# LightSensor.net
KiCad netlist of a schematic drawn in EAGLE
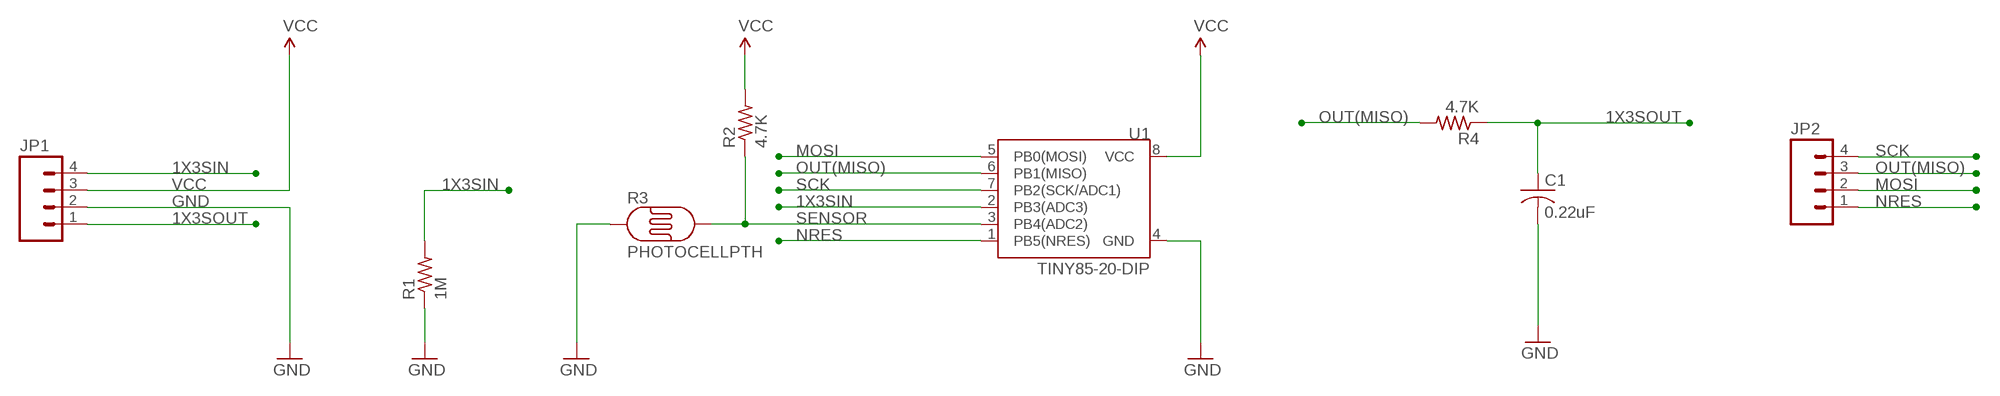
[diagram p0: schematic, sheet 1]

(export (version "E")
  (design (tool "Eeschema 10.0.6"))
  (components
    (comp (ref "C1")
      (value "0.22uF")
      (footprint "eagle-import:C0402")
      (libsource (lib "eagle-import") (part "C-USC0402"))
    )
    (comp (ref "JP1")
      (value "M04PTH")
      (footprint "eagle-import:1X04")
      (libsource (lib "eagle-import") (part "M04PTH"))
    )
    (comp (ref "JP2")
      (value "M04PTH")
      (footprint "eagle-import:1X04")
      (libsource (lib "eagle-import") (part "M04PTH"))
    )
    (comp (ref "R1")
      (value "1M")
      (footprint "eagle-import:R0603")
      (libsource (lib "eagle-import") (part "R-US_R0603"))
    )
    (comp (ref "R2")
      (value "4.7K")
      (footprint "eagle-import:R0603")
      (libsource (lib "eagle-import") (part "R-US_R0603"))
    )
    (comp (ref "R3")
      (value "PHOTOCELLPTH")
      (footprint "eagle-import:PHOTOCELL")
      (libsource (lib "eagle-import") (part "PHOTOCELLPTH"))
    )
    (comp (ref "R4")
      (value "4.7K")
      (footprint "eagle-import:R0603")
      (libsource (lib "eagle-import") (part "R-US_R0603"))
    )
    (comp (ref "U1")
      (value "TINY85-20-DIP")
      (footprint "eagle-import:DIP08")
      (libsource (lib "eagle-import") (part "ATTINY45TINY85-20-DIP"))
    )
  )
  (nets
    (net (code "1") (name "/1X3SIN") (class "Default")
      (node (ref "JP1") (pin "4") (pinfunction "4_4") (pintype "passive"))
      (node (ref "R1") (pin "2") (pinfunction "2_2") (pintype "passive"))
      (node (ref "U1") (pin "2") (pinfunction "PB3(ADC3)_2") (pintype "bidirectional"))
    )
    (net (code "2") (name "/1X3SOUT") (class "Default")
      (node (ref "C1") (pin "1") (pinfunction "1_1") (pintype "passive"))
      (node (ref "JP1") (pin "1") (pinfunction "1_1") (pintype "passive"))
      (node (ref "R4") (pin "1") (pinfunction "1_1") (pintype "passive"))
    )
    (net (code "3") (name "/MOSI") (class "Default")
      (node (ref "JP2") (pin "2") (pinfunction "2_2") (pintype "passive"))
      (node (ref "U1") (pin "5") (pinfunction "PB0(MOSI)_5") (pintype "bidirectional"))
    )
    (net (code "4") (name "/NRES") (class "Default")
      (node (ref "JP2") (pin "1") (pinfunction "1_1") (pintype "passive"))
      (node (ref "U1") (pin "1") (pinfunction "PB5(NRES)_1") (pintype "bidirectional"))
    )
    (net (code "5") (name "/OUT(MISO)") (class "Default")
      (node (ref "JP2") (pin "3") (pinfunction "3_3") (pintype "passive"))
      (node (ref "R4") (pin "2") (pinfunction "2_2") (pintype "passive"))
      (node (ref "U1") (pin "6") (pinfunction "PB1(MISO)_6") (pintype "bidirectional"))
    )
    (net (code "6") (name "/SCK") (class "Default")
      (node (ref "JP2") (pin "4") (pinfunction "4_4") (pintype "passive"))
      (node (ref "U1") (pin "7") (pinfunction "PB2(SCK/ADC1)_7") (pintype "bidirectional"))
    )
    (net (code "7") (name "/SENSOR") (class "Default")
      (node (ref "R2") (pin "1") (pinfunction "1_1") (pintype "passive"))
      (node (ref "R3") (pin "2") (pinfunction "P$2_2") (pintype "bidirectional"))
      (node (ref "U1") (pin "3") (pinfunction "PB4(ADC2)_3") (pintype "bidirectional"))
    )
    (net (code "8") (name "GND") (class "Default")
      (node (ref "C1") (pin "2") (pinfunction "2_2") (pintype "passive"))
      (node (ref "JP1") (pin "2") (pinfunction "2_2") (pintype "passive"))
      (node (ref "R1") (pin "1") (pinfunction "1_1") (pintype "passive"))
      (node (ref "R3") (pin "1") (pinfunction "P$1_1") (pintype "bidirectional"))
      (node (ref "U1") (pin "4") (pinfunction "GND_4") (pintype "bidirectional"))
    )
    (net (code "9") (name "VCC") (class "Default")
      (node (ref "JP1") (pin "3") (pinfunction "3_3") (pintype "passive"))
      (node (ref "R2") (pin "2") (pinfunction "2_2") (pintype "passive"))
      (node (ref "U1") (pin "8") (pinfunction "VCC_8") (pintype "bidirectional"))
    )
  )
)
